# ArduIR.net
KiCad netlist of a schematic drawn in EAGLE
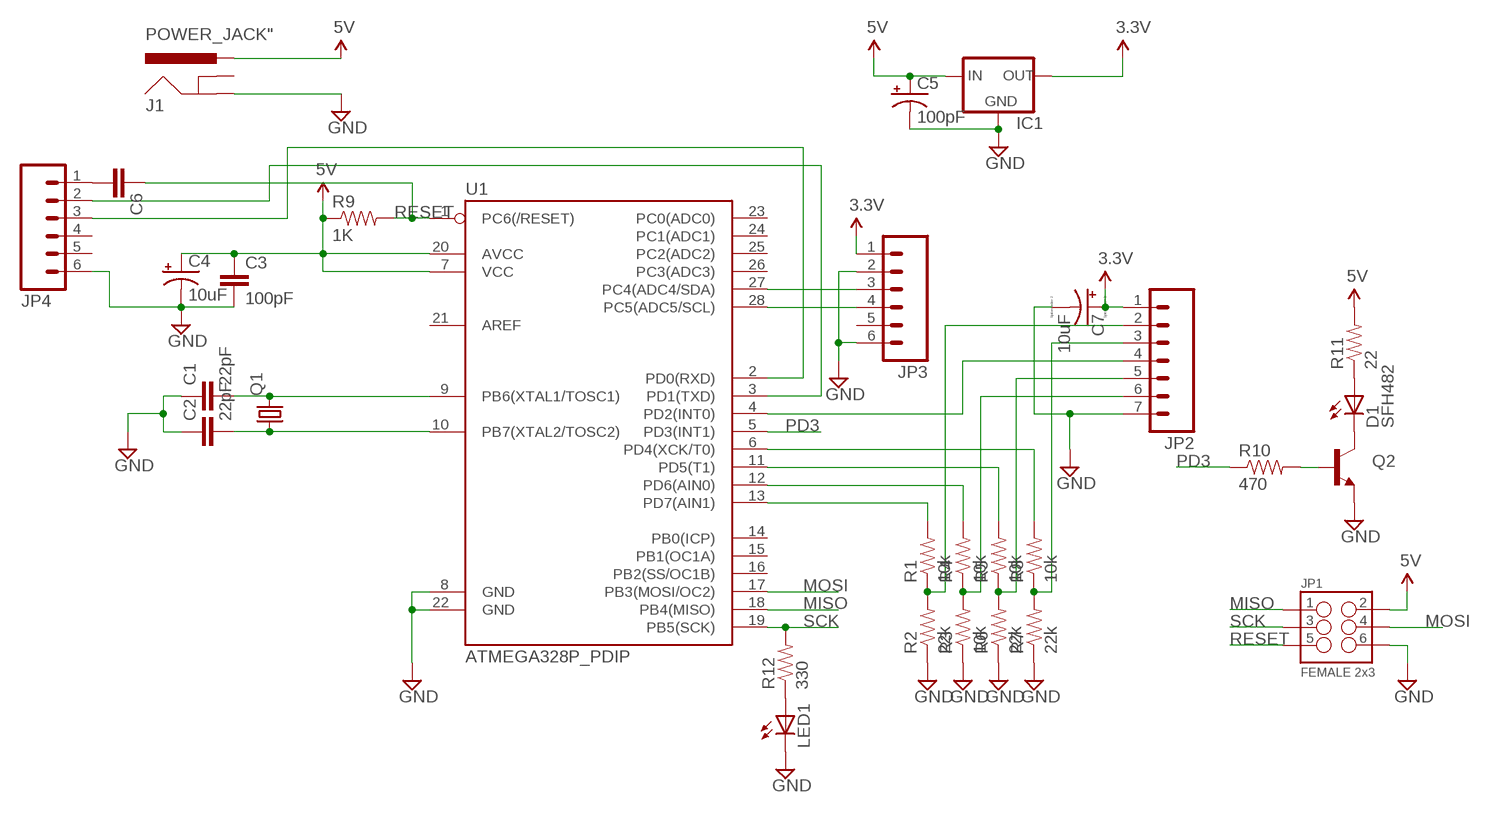
[diagram p0: schematic, sheet 1]

(export (version "E")
  (design (tool "Eeschema 10.0.6"))
  (components
    (comp (ref "C1")
      (value "22pF")
      (footprint "eagle-import:CAP-PTH-SMALL")
      (libsource (lib "eagle-import") (part "CAPPTH"))
    )
    (comp (ref "C2")
      (value "22pF")
      (footprint "eagle-import:CAP-PTH-SMALL")
      (libsource (lib "eagle-import") (part "CAPPTH"))
    )
    (comp (ref "C3")
      (value "100pF")
      (footprint "eagle-import:CAP-PTH-SMALL-KIT")
      (libsource (lib "eagle-import") (part "0.1UF-50V-20%(PTH)KIT-EZ"))
    )
    (comp (ref "C4")
      (value "10uF")
      (footprint "eagle-import:CPOL-RADIAL-10UF-25V")
      (libsource (lib "eagle-import") (part "CAP_POLPTH2"))
    )
    (comp (ref "C5")
      (value "100pF")
      (footprint "eagle-import:CPOL-RADIAL-10UF-25V")
      (libsource (lib "eagle-import") (part "CAP_POLPTH2"))
    )
    (comp (ref "C6")
      (value "0.1UF-50V-20%(PTH)KIT-EZ")
      (footprint "eagle-import:CAP-PTH-SMALL-KIT")
      (libsource (lib "eagle-import") (part "0.1UF-50V-20%(PTH)KIT-EZ"))
    )
    (comp (ref "C7")
      (value "10uF")
      (footprint "eagle-import:E15-5")
      (libsource (lib "eagle-import") (part "CPOL-USE15-5AXIAL"))
    )
    (comp (ref "D1")
      (value "SFH482")
      (footprint "eagle-import:SFH482")
      (libsource (lib "eagle-import") (part "SFH482"))
    )
    (comp (ref "IC1")
      (value "REGULATORTO220")
      (footprint "eagle-import:L4931_REGULATOR")
      (libsource (lib "eagle-import") (part "REGULATORTO220"))
    )
    (comp (ref "J1")
      (value "POWER_JACK\"")
      (footprint "eagle-import:POWER_JACK")
      (libsource (lib "eagle-import") (part "POWER_JACK{dblquote}"))
    )
    (comp (ref "JP1")
      (value "FEMALE 2x3")
      (footprint "eagle-import:2X3")
      (libsource (lib "eagle-import") (part "M03X2FEMALE"))
    )
    (comp (ref "JP2")
      (value "M07")
      (footprint "eagle-import:1X07")
      (libsource (lib "eagle-import") (part "M07"))
    )
    (comp (ref "JP3")
      (value "M06SILK_FEMALE_PTH")
      (footprint "eagle-import:1X06")
      (libsource (lib "eagle-import") (part "M06SILK_FEMALE_PTH"))
    )
    (comp (ref "JP4")
      (value "M06SILK_FEMALE_PTH")
      (footprint "eagle-import:1X06")
      (libsource (lib "eagle-import") (part "M06SILK_FEMALE_PTH"))
    )
    (comp (ref "LED1")
      (value "LED5MM")
      (footprint "eagle-import:LED5MM")
      (libsource (lib "eagle-import") (part "LED5MM"))
    )
    (comp (ref "Q1")
      (value "CRYSTALHC49US")
      (footprint "eagle-import:HC49US")
      (libsource (lib "eagle-import") (part "CRYSTALHC49US"))
    )
    (comp (ref "Q2")
      (value "TRANSISTOR_NPNTO-92-AMMO")
      (footprint "eagle-import:TO-92-AMMO")
      (libsource (lib "eagle-import") (part "TRANSISTOR_NPNTO-92-AMMO"))
    )
    (comp (ref "R1")
      (value "10k")
      (footprint "eagle-import:AXIAL-0.1EZ")
      (libsource (lib "eagle-import") (part "10KOHM-1/4W-1%(PTH)VERT-KIT"))
    )
    (comp (ref "R2")
      (value "22k")
      (footprint "eagle-import:AXIAL-0.1EZ")
      (libsource (lib "eagle-import") (part "10KOHM-1/4W-1%(PTH)VERT-KIT"))
    )
    (comp (ref "R3")
      (value "10k")
      (footprint "eagle-import:AXIAL-0.1EZ")
      (libsource (lib "eagle-import") (part "10KOHM-1/4W-1%(PTH)VERT-KIT"))
    )
    (comp (ref "R4")
      (value "10k")
      (footprint "eagle-import:AXIAL-0.1EZ")
      (libsource (lib "eagle-import") (part "10KOHM-1/4W-1%(PTH)VERT-KIT"))
    )
    (comp (ref "R5")
      (value "10k")
      (footprint "eagle-import:AXIAL-0.1EZ")
      (libsource (lib "eagle-import") (part "10KOHM-1/4W-1%(PTH)VERT-KIT"))
    )
    (comp (ref "R6")
      (value "22k")
      (footprint "eagle-import:AXIAL-0.1EZ")
      (libsource (lib "eagle-import") (part "10KOHM-1/4W-1%(PTH)VERT-KIT"))
    )
    (comp (ref "R7")
      (value "22k")
      (footprint "eagle-import:AXIAL-0.1EZ")
      (libsource (lib "eagle-import") (part "10KOHM-1/4W-1%(PTH)VERT-KIT"))
    )
    (comp (ref "R8")
      (value "10k")
      (footprint "eagle-import:AXIAL-0.1EZ")
      (libsource (lib "eagle-import") (part "10KOHM-1/4W-1%(PTH)VERT-KIT"))
    )
    (comp (ref "R9")
      (value "1K")
      (footprint "eagle-import:AXIAL-0.1EZ")
      (libsource (lib "eagle-import") (part "1KOHM-1/4W-1%(PTH)VERT-KIT"))
    )
    (comp (ref "R10")
      (value "470")
      (footprint "eagle-import:AXIAL-0.3EZ")
      (libsource (lib "eagle-import") (part "1KOHM-1/4W-1%(PTH)HORIZ-KIT"))
    )
    (comp (ref "R11")
      (value "22")
      (footprint "eagle-import:AXIAL-0.3EZ")
      (libsource (lib "eagle-import") (part "1KOHM-1/4W-1%(PTH)HORIZ-KIT"))
    )
    (comp (ref "R12")
      (value "330")
      (footprint "eagle-import:AXIAL-0.1EZ")
      (libsource (lib "eagle-import") (part "10KOHM-1/4W-1%(PTH)VERT-KIT"))
    )
    (comp (ref "U1")
      (value "ATMEGA328P_PDIP")
      (footprint "eagle-import:DIL28-3")
      (libsource (lib "eagle-import") (part "ATMEGA328P_PDIP"))
    )
  )
  (nets
    (net (code "1") (name "/MISO") (class "Default")
      (node (ref "JP1") (pin "1") (pinfunction "1_1") (pintype "bidirectional"))
      (node (ref "U1") (pin "18") (pinfunction "PB4(MISO)_18") (pintype "bidirectional"))
    )
    (net (code "2") (name "/MOSI") (class "Default")
      (node (ref "JP1") (pin "4") (pinfunction "4_4") (pintype "bidirectional"))
      (node (ref "U1") (pin "17") (pinfunction "PB3(MOSI/OC2)_17") (pintype "bidirectional"))
    )
    (net (code "3") (name "/PD3") (class "Default")
      (node (ref "R10") (pin "P$1") (pinfunction "1_P$1") (pintype "passive"))
      (node (ref "U1") (pin "5") (pinfunction "PD3(INT1)_5") (pintype "bidirectional"))
    )
    (net (code "4") (name "/RESET") (class "Default")
      (node (ref "C6") (pin "1") (pinfunction "1_1") (pintype "passive"))
      (node (ref "JP1") (pin "5") (pinfunction "5_5") (pintype "bidirectional"))
      (node (ref "R9") (pin "P$2") (pinfunction "2_P$2") (pintype "passive"))
      (node (ref "U1") (pin "1") (pinfunction "PC6(/RESET)_1") (pintype "bidirectional"))
    )
    (net (code "5") (name "/SCK") (class "Default")
      (node (ref "JP1") (pin "3") (pinfunction "3_3") (pintype "bidirectional"))
      (node (ref "R12") (pin "P$2") (pinfunction "2_P$2") (pintype "passive"))
      (node (ref "U1") (pin "19") (pinfunction "PB5(SCK)_19") (pintype "bidirectional"))
    )
    (net (code "6") (name "3.3V") (class "Default")
      (node (ref "C7") (pin "+") (pinfunction "+_+") (pintype "passive"))
      (node (ref "IC1") (pin "OUT") (pinfunction "OUT_OUT") (pintype "passive"))
      (node (ref "JP2") (pin "1") (pinfunction "1_1") (pintype "passive"))
      (node (ref "JP3") (pin "1") (pinfunction "1_1") (pintype "passive"))
    )
    (net (code "7") (name "5V") (class "Default")
      (node (ref "C3") (pin "1") (pinfunction "1_1") (pintype "passive"))
      (node (ref "C4") (pin "1") (pinfunction "+_1") (pintype "passive"))
      (node (ref "C5") (pin "1") (pinfunction "+_1") (pintype "passive"))
      (node (ref "IC1") (pin "IN") (pinfunction "IN_IN") (pintype "input"))
      (node (ref "J1") (pin "PWR") (pinfunction "PWR_PWR") (pintype "bidirectional"))
      (node (ref "JP1") (pin "2") (pinfunction "2_2") (pintype "bidirectional"))
      (node (ref "R11") (pin "P$2") (pinfunction "2_P$2") (pintype "passive"))
      (node (ref "R9") (pin "P$1") (pinfunction "1_P$1") (pintype "passive"))
      (node (ref "U1") (pin "20") (pinfunction "AVCC_20") (pintype "bidirectional"))
      (node (ref "U1") (pin "7") (pinfunction "VCC_7") (pintype "bidirectional"))
    )
    (net (code "8") (name "GND") (class "Default")
      (node (ref "C1") (pin "1") (pinfunction "1_1") (pintype "passive"))
      (node (ref "C2") (pin "1") (pinfunction "1_1") (pintype "passive"))
      (node (ref "C3") (pin "2") (pinfunction "2_2") (pintype "passive"))
      (node (ref "C4") (pin "2") (pinfunction "-_2") (pintype "passive"))
      (node (ref "C5") (pin "2") (pinfunction "-_2") (pintype "passive"))
      (node (ref "C7") (pin "-") (pinfunction "-_-") (pintype "passive"))
      (node (ref "IC1") (pin "GND") (pinfunction "GND_GND") (pintype "input"))
      (node (ref "J1") (pin "GND") (pinfunction "GND_GND") (pintype "bidirectional"))
      (node (ref "JP1") (pin "6") (pinfunction "6_6") (pintype "bidirectional"))
      (node (ref "JP2") (pin "7") (pinfunction "7_7") (pintype "passive"))
      (node (ref "JP3") (pin "2") (pinfunction "2_2") (pintype "passive"))
      (node (ref "JP3") (pin "6") (pinfunction "6_6") (pintype "passive"))
      (node (ref "JP4") (pin "6") (pinfunction "6_6") (pintype "passive"))
      (node (ref "LED1") (pin "K") (pinfunction "C_K") (pintype "passive"))
      (node (ref "Q2") (pin "1") (pinfunction "E_1") (pintype "passive"))
      (node (ref "R2") (pin "P$1") (pinfunction "1_P$1") (pintype "passive"))
      (node (ref "R3") (pin "P$1") (pinfunction "1_P$1") (pintype "passive"))
      (node (ref "R6") (pin "P$1") (pinfunction "1_P$1") (pintype "passive"))
      (node (ref "R7") (pin "P$1") (pinfunction "1_P$1") (pintype "passive"))
      (node (ref "U1") (pin "22") (pinfunction "GND_22") (pintype "bidirectional"))
      (node (ref "U1") (pin "8") (pinfunction "GND_8") (pintype "bidirectional"))
    )
    (net (code "9") (name "Net-(C6-Pad2)") (class "Default")
      (node (ref "C6") (pin "2") (pinfunction "2_2") (pintype "passive"))
      (node (ref "JP4") (pin "1") (pinfunction "1_1") (pintype "passive"))
    )
    (net (code "10") (name "Net-(D1-C)") (class "Default")
      (node (ref "D1") (pin "K") (pinfunction "C_K") (pintype "passive"))
      (node (ref "Q2") (pin "3") (pinfunction "C_3") (pintype "passive"))
    )
    (net (code "11") (name "Net-(Q2-B)") (class "Default")
      (node (ref "Q2") (pin "2") (pinfunction "B_2") (pintype "passive"))
      (node (ref "R10") (pin "P$2") (pinfunction "2_P$2") (pintype "passive"))
    )
    (net (code "12") (name "Net-(R1-1)") (class "Default")
      (node (ref "JP2") (pin "2") (pinfunction "2_2") (pintype "passive"))
      (node (ref "R1") (pin "P$1") (pinfunction "1_P$1") (pintype "passive"))
      (node (ref "R2") (pin "P$2") (pinfunction "2_P$2") (pintype "passive"))
    )
    (net (code "13") (name "Net-(R1-2)") (class "Default")
      (node (ref "R1") (pin "P$2") (pinfunction "2_P$2") (pintype "passive"))
      (node (ref "U1") (pin "13") (pinfunction "PD7(AIN1)_13") (pintype "bidirectional"))
    )
    (net (code "14") (name "Net-(R3-2)") (class "Default")
      (node (ref "JP2") (pin "6") (pinfunction "6_6") (pintype "passive"))
      (node (ref "R3") (pin "P$2") (pinfunction "2_P$2") (pintype "passive"))
      (node (ref "R4") (pin "P$1") (pinfunction "1_P$1") (pintype "passive"))
    )
    (net (code "15") (name "Net-(R4-2)") (class "Default")
      (node (ref "R4") (pin "P$2") (pinfunction "2_P$2") (pintype "passive"))
      (node (ref "U1") (pin "12") (pinfunction "PD6(AIN0)_12") (pintype "bidirectional"))
    )
    (net (code "16") (name "Net-(R5-1)") (class "Default")
      (node (ref "JP2") (pin "5") (pinfunction "5_5") (pintype "passive"))
      (node (ref "R5") (pin "P$1") (pinfunction "1_P$1") (pintype "passive"))
      (node (ref "R6") (pin "P$2") (pinfunction "2_P$2") (pintype "passive"))
    )
    (net (code "17") (name "Net-(R5-2)") (class "Default")
      (node (ref "R5") (pin "P$2") (pinfunction "2_P$2") (pintype "passive"))
      (node (ref "U1") (pin "11") (pinfunction "PD5(T1)_11") (pintype "bidirectional"))
    )
    (net (code "18") (name "Net-(R7-2)") (class "Default")
      (node (ref "JP2") (pin "3") (pinfunction "3_3") (pintype "passive"))
      (node (ref "R7") (pin "P$2") (pinfunction "2_P$2") (pintype "passive"))
      (node (ref "R8") (pin "P$1") (pinfunction "1_P$1") (pintype "passive"))
    )
    (net (code "19") (name "Net-(R8-2)") (class "Default")
      (node (ref "R8") (pin "P$2") (pinfunction "2_P$2") (pintype "passive"))
      (node (ref "U1") (pin "6") (pinfunction "PD4(XCK/T0)_6") (pintype "bidirectional"))
    )
    (net (code "20") (name "Net-(R11-1)") (class "Default")
      (node (ref "D1") (pin "A") (pinfunction "A_A") (pintype "passive"))
      (node (ref "R11") (pin "P$1") (pinfunction "1_P$1") (pintype "passive"))
    )
    (net (code "21") (name "Net-(R12-1)") (class "Default")
      (node (ref "LED1") (pin "A") (pinfunction "A_A") (pintype "passive"))
      (node (ref "R12") (pin "P$1") (pinfunction "1_P$1") (pintype "passive"))
    )
    (net (code "22") (name "Net-(U1-PB6(XTAL1{slash}TOSC1))") (class "Default")
      (node (ref "C1") (pin "2") (pinfunction "2_2") (pintype "passive"))
      (node (ref "Q1") (pin "2") (pinfunction "2_2") (pintype "passive"))
      (node (ref "U1") (pin "9") (pinfunction "PB6(XTAL1/TOSC1)_9") (pintype "bidirectional"))
    )
    (net (code "23") (name "Net-(U1-PB7(XTAL2{slash}TOSC2))") (class "Default")
      (node (ref "C2") (pin "2") (pinfunction "2_2") (pintype "passive"))
      (node (ref "Q1") (pin "1") (pinfunction "1_1") (pintype "passive"))
      (node (ref "U1") (pin "10") (pinfunction "PB7(XTAL2/TOSC2)_10") (pintype "bidirectional"))
    )
    (net (code "24") (name "Net-(U1-PC4(ADC4{slash}SDA))") (class "Default")
      (node (ref "JP3") (pin "3") (pinfunction "3_3") (pintype "passive"))
      (node (ref "U1") (pin "27") (pinfunction "PC4(ADC4/SDA)_27") (pintype "bidirectional"))
    )
    (net (code "25") (name "Net-(U1-PC5(ADC5{slash}SCL))") (class "Default")
      (node (ref "JP3") (pin "4") (pinfunction "4_4") (pintype "passive"))
      (node (ref "U1") (pin "28") (pinfunction "PC5(ADC5/SCL)_28") (pintype "bidirectional"))
    )
    (net (code "26") (name "Net-(U1-PD0(RXD))") (class "Default")
      (node (ref "JP4") (pin "3") (pinfunction "3_3") (pintype "passive"))
      (node (ref "U1") (pin "2") (pinfunction "PD0(RXD)_2") (pintype "bidirectional"))
    )
    (net (code "27") (name "Net-(U1-PD1(TXD))") (class "Default")
      (node (ref "JP4") (pin "2") (pinfunction "2_2") (pintype "passive"))
      (node (ref "U1") (pin "3") (pinfunction "PD1(TXD)_3") (pintype "bidirectional"))
    )
    (net (code "28") (name "Net-(U1-PD2(INT0))") (class "Default")
      (node (ref "JP2") (pin "4") (pinfunction "4_4") (pintype "passive"))
      (node (ref "U1") (pin "4") (pinfunction "PD2(INT0)_4") (pintype "bidirectional"))
    )
    (net (code "29") (name "unconnected-(J1-PadGNDBREAK)") (class "Default")
      (node (ref "J1") (pin "GNDBREAK") (pinfunction "GNDBREAK_GNDBREAK") (pintype "bidirectional"))
    )
    (net (code "30") (name "unconnected-(JP3-Pad5)") (class "Default")
      (node (ref "JP3") (pin "5") (pinfunction "5_5") (pintype "passive"))
    )
    (net (code "31") (name "unconnected-(JP4-Pad4)") (class "Default")
      (node (ref "JP4") (pin "4") (pinfunction "4_4") (pintype "passive"))
    )
    (net (code "32") (name "unconnected-(JP4-Pad5)") (class "Default")
      (node (ref "JP4") (pin "5") (pinfunction "5_5") (pintype "passive"))
    )
    (net (code "33") (name "unconnected-(U1-AREF-Pad21)") (class "Default")
      (node (ref "U1") (pin "21") (pinfunction "AREF_21") (pintype "bidirectional"))
    )
    (net (code "34") (name "unconnected-(U1-PB0(ICP)-Pad14)") (class "Default")
      (node (ref "U1") (pin "14") (pinfunction "PB0(ICP)_14") (pintype "bidirectional"))
    )
    (net (code "35") (name "unconnected-(U1-PB1(OC1A)-Pad15)") (class "Default")
      (node (ref "U1") (pin "15") (pinfunction "PB1(OC1A)_15") (pintype "bidirectional"))
    )
    (net (code "36") (name "unconnected-(U1-PB2(SS{slash}OC1B)-Pad16)") (class "Default")
      (node (ref "U1") (pin "16") (pinfunction "PB2(SS/OC1B)_16") (pintype "bidirectional"))
    )
    (net (code "37") (name "unconnected-(U1-PC0(ADC0)-Pad23)") (class "Default")
      (node (ref "U1") (pin "23") (pinfunction "PC0(ADC0)_23") (pintype "bidirectional"))
    )
    (net (code "38") (name "unconnected-(U1-PC1(ADC1)-Pad24)") (class "Default")
      (node (ref "U1") (pin "24") (pinfunction "PC1(ADC1)_24") (pintype "bidirectional"))
    )
    (net (code "39") (name "unconnected-(U1-PC2(ADC2)-Pad25)") (class "Default")
      (node (ref "U1") (pin "25") (pinfunction "PC2(ADC2)_25") (pintype "bidirectional"))
    )
    (net (code "40") (name "unconnected-(U1-PC3(ADC3)-Pad26)") (class "Default")
      (node (ref "U1") (pin "26") (pinfunction "PC3(ADC3)_26") (pintype "bidirectional"))
    )
  )
)
